# main.net
KiCad netlist of a schematic drawn in Altium Designer
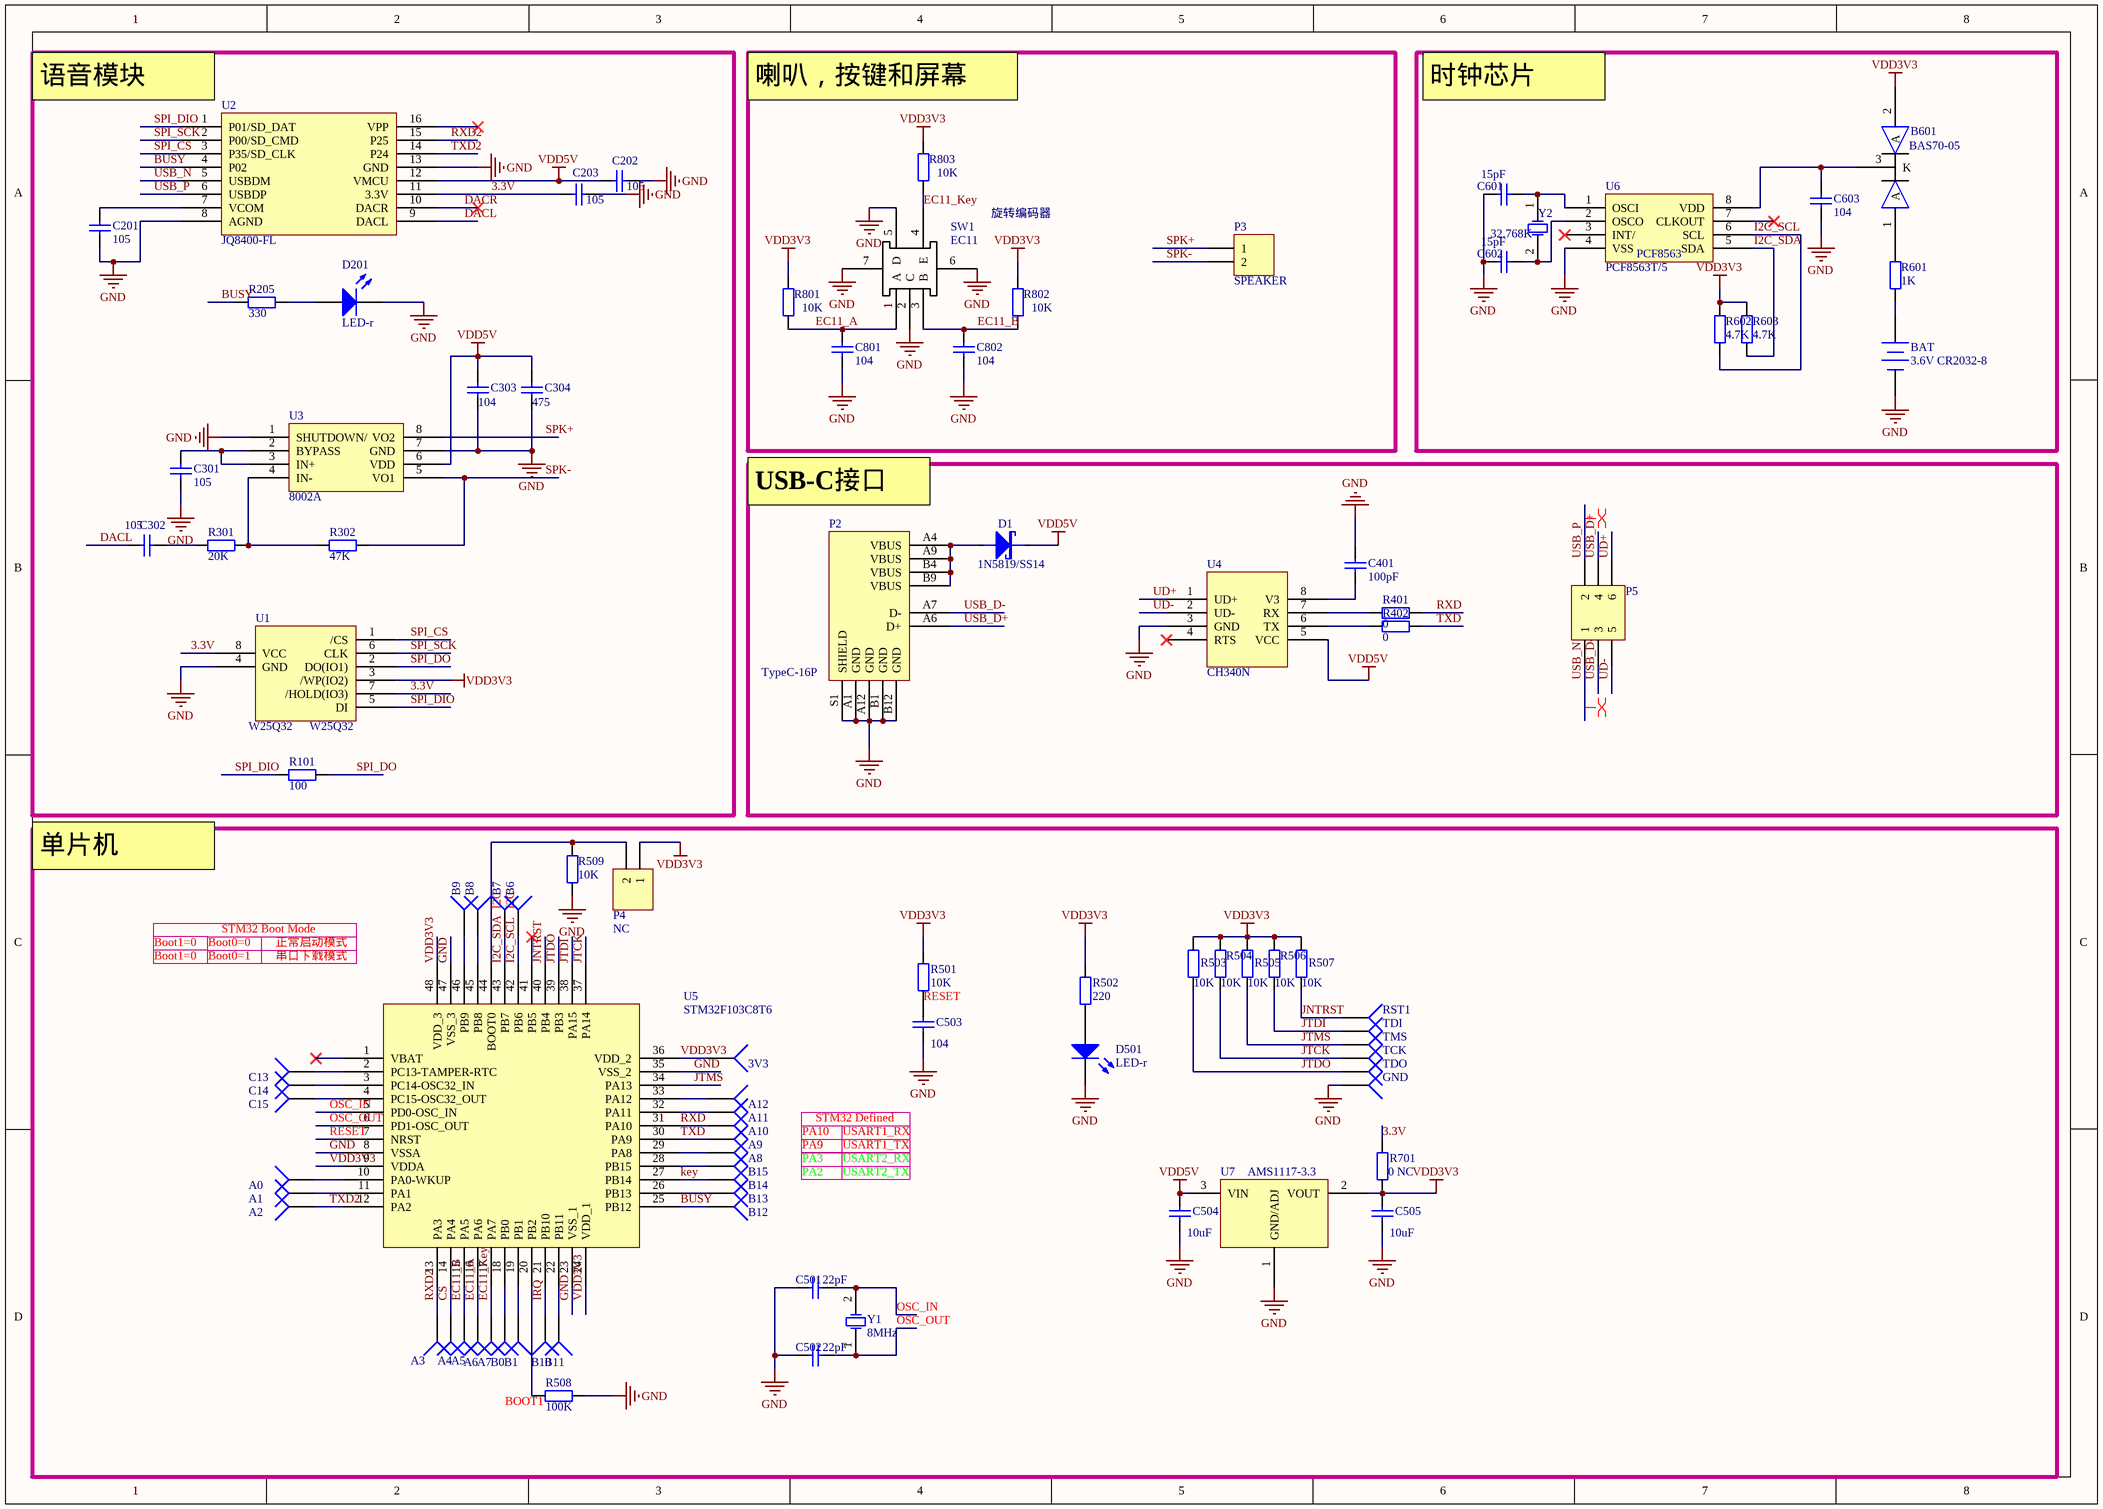
[diagram p0: main.SchDoc]

(export (version "E")
  (design (tool "Eeschema 10.0.6"))
  (components
    (comp (ref "3V3")
      (value "Socket")
      (footprint "TP")
      (fields (field (name "PUBLISHER") "Altium Limited"))
      (libsource (lib "Miscellaneous Connectors") (part "Socket"))
    )
    (comp (ref "A0")
      (value "Socket")
      (footprint "TP")
      (fields (field (name "PUBLISHER") "Altium Limited"))
      (libsource (lib "Miscellaneous Connectors") (part "Socket"))
    )
    (comp (ref "A1")
      (value "Socket")
      (footprint "TP")
      (fields (field (name "PUBLISHER") "Altium Limited"))
      (libsource (lib "Miscellaneous Connectors") (part "Socket"))
    )
    (comp (ref "A2")
      (value "Socket")
      (footprint "TP")
      (fields (field (name "PUBLISHER") "Altium Limited"))
      (libsource (lib "Miscellaneous Connectors") (part "Socket"))
    )
    (comp (ref "A3")
      (value "Socket")
      (footprint "TP")
      (fields (field (name "PUBLISHER") "Altium Limited"))
      (libsource (lib "Miscellaneous Connectors") (part "Socket"))
    )
    (comp (ref "A4")
      (value "Socket")
      (footprint "TP")
      (fields (field (name "PUBLISHER") "Altium Limited"))
      (libsource (lib "Miscellaneous Connectors") (part "Socket"))
    )
    (comp (ref "A5")
      (value "Socket")
      (footprint "TP")
      (fields (field (name "PUBLISHER") "Altium Limited"))
      (libsource (lib "Miscellaneous Connectors") (part "Socket"))
    )
    (comp (ref "A6")
      (value "Socket")
      (footprint "TP")
      (fields (field (name "PUBLISHER") "Altium Limited"))
      (libsource (lib "Miscellaneous Connectors") (part "Socket"))
    )
    (comp (ref "A7")
      (value "Socket")
      (footprint "TP")
      (fields (field (name "PUBLISHER") "Altium Limited"))
      (libsource (lib "Miscellaneous Connectors") (part "Socket"))
    )
    (comp (ref "A8")
      (value "Socket")
      (footprint "TP")
      (fields (field (name "PUBLISHER") "Altium Limited"))
      (libsource (lib "Miscellaneous Connectors") (part "Socket"))
    )
    (comp (ref "A9")
      (value "Socket")
      (footprint "TP")
      (fields (field (name "PUBLISHER") "Altium Limited"))
      (libsource (lib "Miscellaneous Connectors") (part "Socket"))
    )
    (comp (ref "A10")
      (value "Socket")
      (footprint "TP")
      (fields (field (name "PUBLISHER") "Altium Limited"))
      (libsource (lib "Miscellaneous Connectors") (part "Socket"))
    )
    (comp (ref "A11")
      (value "Socket")
      (footprint "TP")
      (fields (field (name "PUBLISHER") "Altium Limited"))
      (libsource (lib "Miscellaneous Connectors") (part "Socket"))
    )
    (comp (ref "A12")
      (value "Socket")
      (footprint "TP")
      (fields (field (name "PUBLISHER") "Altium Limited"))
      (libsource (lib "Miscellaneous Connectors") (part "Socket"))
    )
    (comp (ref "B0")
      (value "Socket")
      (footprint "TP")
      (fields (field (name "PUBLISHER") "Altium Limited"))
      (libsource (lib "Miscellaneous Connectors") (part "Socket"))
    )
    (comp (ref "B1")
      (value "Socket")
      (footprint "TP")
      (fields (field (name "PUBLISHER") "Altium Limited"))
      (libsource (lib "Miscellaneous Connectors") (part "Socket"))
    )
    (comp (ref "B6")
      (value "Socket")
      (footprint "TP")
      (fields (field (name "PUBLISHER") "Altium Limited"))
      (libsource (lib "Miscellaneous Connectors") (part "Socket"))
    )
    (comp (ref "B7")
      (value "Socket")
      (footprint "TP")
      (fields (field (name "PUBLISHER") "Altium Limited"))
      (libsource (lib "Miscellaneous Connectors") (part "Socket"))
    )
    (comp (ref "B8")
      (value "Socket")
      (footprint "TP")
      (fields (field (name "PUBLISHER") "Altium Limited"))
      (libsource (lib "Miscellaneous Connectors") (part "Socket"))
    )
    (comp (ref "B9")
      (value "Socket")
      (footprint "TP")
      (fields (field (name "PUBLISHER") "Altium Limited"))
      (libsource (lib "Miscellaneous Connectors") (part "Socket"))
    )
    (comp (ref "B10")
      (value "Socket")
      (footprint "TP")
      (fields (field (name "PUBLISHER") "Altium Limited"))
      (libsource (lib "Miscellaneous Connectors") (part "Socket"))
    )
    (comp (ref "B11")
      (value "Socket")
      (footprint "TP")
      (fields (field (name "PUBLISHER") "Altium Limited"))
      (libsource (lib "Miscellaneous Connectors") (part "Socket"))
    )
    (comp (ref "B12")
      (value "Socket")
      (footprint "TP")
      (fields (field (name "PUBLISHER") "Altium Limited"))
      (libsource (lib "Miscellaneous Connectors") (part "Socket"))
    )
    (comp (ref "B13")
      (value "Socket")
      (footprint "TP")
      (fields (field (name "PUBLISHER") "Altium Limited"))
      (libsource (lib "Miscellaneous Connectors") (part "Socket"))
    )
    (comp (ref "B14")
      (value "Socket")
      (footprint "TP")
      (fields (field (name "PUBLISHER") "Altium Limited"))
      (libsource (lib "Miscellaneous Connectors") (part "Socket"))
    )
    (comp (ref "B15")
      (value "Socket")
      (footprint "TP")
      (fields (field (name "PUBLISHER") "Altium Limited"))
      (libsource (lib "Miscellaneous Connectors") (part "Socket"))
    )
    (comp (ref "B601")
      (value "BAS70-05")
      (footprint "SMT_TRIODE_NPN")
      (description "贴片三极管  丝印75")
      (libsource (lib "Hardware") (part "BAS70 74"))
    )
    (comp (ref "BAT")
      (value "3.6V CR2032-8")
      (footprint "CR2032-8")
      (description "电池座 半圆形")
      (fields (field (name "PUBLISHER") "Altium Limited"))
      (libsource (lib "Miscellaneous Devices") (part "Battery"))
    )
    (comp (ref "C13")
      (value "Socket")
      (footprint "TP")
      (fields (field (name "PUBLISHER") "Altium Limited"))
      (libsource (lib "Miscellaneous Connectors") (part "Socket"))
    )
    (comp (ref "C14")
      (value "Socket")
      (footprint "TP")
      (fields (field (name "PUBLISHER") "Altium Limited"))
      (libsource (lib "Miscellaneous Connectors") (part "Socket"))
    )
    (comp (ref "C15")
      (value "Socket")
      (footprint "TP")
      (fields (field (name "PUBLISHER") "Altium Limited"))
      (libsource (lib "Miscellaneous Connectors") (part "Socket"))
    )
    (comp (ref "C201")
      (value "105")
      (footprint "0603_CAP")
      (description "Capacitor 0603")
      (fields (field (name "PUBLISHER") "Altium Limited"))
      (libsource (lib "Miscellaneous Devices") (part "Cap"))
    )
    (comp (ref "C202")
      (value "105")
      (footprint "0603_CAP")
      (description "Capacitor 0603")
      (fields (field (name "PUBLISHER") "Altium Limited"))
      (libsource (lib "Miscellaneous Devices") (part "Cap"))
    )
    (comp (ref "C203")
      (value "105")
      (footprint "0603_CAP")
      (description "Capacitor 0603")
      (fields (field (name "PUBLISHER") "Altium Limited"))
      (libsource (lib "Miscellaneous Devices") (part "Cap"))
    )
    (comp (ref "C301")
      (value "105")
      (footprint "0603_CAP")
      (description "Capacitor 0603")
      (fields (field (name "PUBLISHER") "Altium Limited"))
      (libsource (lib "Miscellaneous Devices") (part "Cap"))
    )
    (comp (ref "C302")
      (value "105")
      (footprint "0603_CAP")
      (description "Capacitor 0603")
      (fields (field (name "PUBLISHER") "Altium Limited"))
      (libsource (lib "Miscellaneous Devices") (part "Cap"))
    )
    (comp (ref "C303")
      (value "104")
      (footprint "0603_CAP")
      (description "Capacitor 0603")
      (fields (field (name "PUBLISHER") "Altium Limited"))
      (libsource (lib "Miscellaneous Devices") (part "Cap"))
    )
    (comp (ref "C304")
      (value "475")
      (footprint "0603_CAP")
      (description "Capacitor 0603")
      (fields (field (name "PUBLISHER") "Altium Limited"))
      (libsource (lib "Miscellaneous Devices") (part "Cap"))
    )
    (comp (ref "C401")
      (value "100pF")
      (footprint "0603_CAP")
      (description "Capacitor 0603")
      (fields (field (name "PUBLISHER") "Altium Limited"))
      (libsource (lib "Miscellaneous Devices") (part "Cap"))
    )
    (comp (ref "C501")
      (value "22pF")
      (footprint "0603_CAP")
      (description "Capacitor 0603")
      (fields (field (name "PUBLISHER") "Altium Limited"))
      (libsource (lib "Miscellaneous Devices") (part "Cap"))
    )
    (comp (ref "C502")
      (value "22pF")
      (footprint "0603_CAP")
      (description "Capacitor 0603")
      (fields (field (name "PUBLISHER") "Altium Limited"))
      (libsource (lib "Miscellaneous Devices") (part "Cap"))
    )
    (comp (ref "C503")
      (value "104")
      (footprint "0603_CAP")
      (description "Capacitor 0603")
      (fields (field (name "PUBLISHER") "Altium Limited"))
      (libsource (lib "Miscellaneous Devices") (part "Cap"))
    )
    (comp (ref "C504")
      (value "10uF")
      (footprint "0603_CAP")
      (description "Capacitor 0603")
      (fields (field (name "PUBLISHER") "Altium Limited"))
      (libsource (lib "Miscellaneous Devices") (part "Cap"))
    )
    (comp (ref "C505")
      (value "10uF")
      (footprint "0603_CAP")
      (description "Capacitor 0603")
      (fields (field (name "PUBLISHER") "Altium Limited"))
      (libsource (lib "Miscellaneous Devices") (part "Cap"))
    )
    (comp (ref "C601")
      (value "15pF")
      (footprint "0603_CAP")
      (description "Capacitor 0603")
      (fields (field (name "PUBLISHER") "Altium Limited"))
      (libsource (lib "Miscellaneous Devices") (part "Cap"))
    )
    (comp (ref "C602")
      (value "15pF")
      (footprint "0603_CAP")
      (description "Capacitor 0603")
      (fields (field (name "PUBLISHER") "Altium Limited"))
      (libsource (lib "Miscellaneous Devices") (part "Cap"))
    )
    (comp (ref "C603")
      (value "104")
      (footprint "0603_CAP")
      (description "Capacitor 0603")
      (fields (field (name "PUBLISHER") "Altium Limited"))
      (libsource (lib "Miscellaneous Devices") (part "Cap"))
    )
    (comp (ref "C801")
      (value "104")
      (footprint "0603_CAP")
      (description "Capacitor 0603")
      (fields (field (name "PUBLISHER") "Altium Limited"))
      (libsource (lib "Miscellaneous Devices") (part "Cap"))
    )
    (comp (ref "C802")
      (value "104")
      (footprint "0603_CAP")
      (description "Capacitor 0603")
      (fields (field (name "PUBLISHER") "Altium Limited"))
      (libsource (lib "Miscellaneous Devices") (part "Cap"))
    )
    (comp (ref "D1")
      (value "1N5819/SS14")
      (footprint "SMA")
      (description "肖特基整流二极管SOD-323")
      (libsource (lib "Vowstar_Basic_Device") (part "SMT_DIODE_SCHOTTKY_SOD_323"))
    )
    (comp (ref "D201")
      (value "LED-r")
      (footprint "LED-0603")
      (description "NC")
      (fields (field (name "PUBLISHER") "Altium Limited"))
      (libsource (lib "Miscellaneous Devices") (part "LED2"))
    )
    (comp (ref "D501")
      (value "LED-r")
      (footprint "LED-0603")
      (description "NC")
      (fields (field (name "PUBLISHER") "Altium Limited"))
      (libsource (lib "Miscellaneous Devices") (part "LED2"))
    )
    (comp (ref "GND")
      (value "Socket")
      (footprint "TP")
      (fields (field (name "PUBLISHER") "Altium Limited"))
      (libsource (lib "Miscellaneous Connectors") (part "Socket"))
    )
    (comp (ref "P2")
      (value "TypeC-16P")
      (footprint "type-c 16pin")
      (description "TypeC接口16P")
      (libsource (lib "Hardware") (part "TypeC-16P"))
    )
    (comp (ref "P3")
      (value "SPEAKER")
      (footprint "Speaker")
      (description "扬声器")
      (fields (field (name "PUBLISHER") "Altium Limited"))
      (libsource (lib "Miscellaneous Connectors") (part "Header 2"))
    )
    (comp (ref "P4")
      (value "NC")
      (footprint "HDR1X2")
      (description "下载短接口")
      (fields (field (name "PUBLISHER") "Altium Limited"))
      (libsource (lib "") (part "Header 2_1"))
    )
    (comp (ref "P5")
      (value "NC 3X2")
      (footprint "HDR2X3")
      (description "USB跳线接口")
      (fields (field (name "PUBLISHER") "Altium Limited"))
      (libsource (lib "Miscellaneous Connectors") (part "Header 3X2"))
    )
    (comp (ref "R101")
      (value "100")
      (footprint "0603_CAP")
      (description "Resistor 0603")
      (fields (field (name "PUBLISHER") "Altium Limited"))
      (libsource (lib "") (part "Res2_1"))
    )
    (comp (ref "R205")
      (value "330")
      (footprint "0603_CAP")
      (description "Resistor 0603")
      (fields (field (name "PUBLISHER") "Altium Limited"))
      (libsource (lib "") (part "Res2_1"))
    )
    (comp (ref "R301")
      (value "20K")
      (footprint "0603_CAP")
      (description "Resistor 0603")
      (fields (field (name "PUBLISHER") "Altium Limited"))
      (libsource (lib "") (part "Res2_1"))
    )
    (comp (ref "R302")
      (value "47K")
      (footprint "0603_CAP")
      (description "Resistor 0603")
      (fields (field (name "PUBLISHER") "Altium Limited"))
      (libsource (lib "") (part "Res2_1"))
    )
    (comp (ref "R401")
      (value "0")
      (footprint "0603_CAP")
      (description "Resistor 0603")
      (fields (field (name "PUBLISHER") "Altium Limited"))
      (libsource (lib "") (part "Res2_2"))
    )
    (comp (ref "R402")
      (value "0")
      (footprint "0603_CAP")
      (description "Resistor 0603")
      (fields (field (name "PUBLISHER") "Altium Limited"))
      (libsource (lib "") (part "Res2_2"))
    )
    (comp (ref "R501")
      (value "10K")
      (footprint "0603_CAP")
      (description "Resistor 0603")
      (fields (field (name "PUBLISHER") "Altium Limited"))
      (libsource (lib "Miscellaneous Devices") (part "Res2"))
    )
    (comp (ref "R502")
      (value "220")
      (footprint "0603_CAP")
      (description "Resistor 0603")
      (fields (field (name "PUBLISHER") "Altium Limited"))
      (libsource (lib "Miscellaneous Devices") (part "Res2"))
    )
    (comp (ref "R503")
      (value "10K")
      (footprint "0603_CAP")
      (description "Resistor 0603")
      (fields (field (name "PUBLISHER") "Altium Limited"))
      (libsource (lib "Miscellaneous Devices") (part "Res2"))
    )
    (comp (ref "R504")
      (value "10K")
      (footprint "0603_CAP")
      (description "Resistor 0603")
      (fields (field (name "PUBLISHER") "Altium Limited"))
      (libsource (lib "Miscellaneous Devices") (part "Res2"))
    )
    (comp (ref "R505")
      (value "10K")
      (footprint "0603_CAP")
      (description "Resistor 0603")
      (fields (field (name "PUBLISHER") "Altium Limited"))
      (libsource (lib "Miscellaneous Devices") (part "Res2"))
    )
    (comp (ref "R506")
      (value "10K")
      (footprint "0603_CAP")
      (description "Resistor 0603")
      (fields (field (name "PUBLISHER") "Altium Limited"))
      (libsource (lib "Miscellaneous Devices") (part "Res2"))
    )
    (comp (ref "R507")
      (value "10K")
      (footprint "0603_CAP")
      (description "Resistor 0603")
      (fields (field (name "PUBLISHER") "Altium Limited"))
      (libsource (lib "Miscellaneous Devices") (part "Res2"))
    )
    (comp (ref "R508")
      (value "100K")
      (footprint "0603_CAP")
      (description "Resistor 0603")
      (fields (field (name "PUBLISHER") "Altium Limited"))
      (libsource (lib "") (part "Res2_2"))
    )
    (comp (ref "R509")
      (value "10K")
      (footprint "0603_CAP")
      (description "Resistor 0603")
      (fields (field (name "PUBLISHER") "Altium Limited"))
      (libsource (lib "Miscellaneous Devices") (part "Res2"))
    )
    (comp (ref "R601")
      (value "1K")
      (footprint "0603_CAP")
      (description "Resistor 0603")
      (fields (field (name "PUBLISHER") "Altium Limited"))
      (libsource (lib "Miscellaneous Devices") (part "Res2"))
    )
    (comp (ref "R602")
      (value "4.7K")
      (footprint "0603_CAP")
      (description "Resistor 0603")
      (fields (field (name "PUBLISHER") "Altium Limited"))
      (libsource (lib "Miscellaneous Devices") (part "Res2"))
    )
    (comp (ref "R603")
      (value "4.7K")
      (footprint "0603_CAP")
      (description "Resistor 0603")
      (fields (field (name "PUBLISHER") "Altium Limited"))
      (libsource (lib "Miscellaneous Devices") (part "Res2"))
    )
    (comp (ref "R701")
      (value "0 NC")
      (footprint "0603_CAP")
      (description "Resistor 0603")
      (fields (field (name "PUBLISHER") "Altium Limited"))
      (libsource (lib "Miscellaneous Devices") (part "Res2"))
    )
    (comp (ref "R801")
      (value "10K")
      (footprint "0603_CAP")
      (description "Resistor 0603")
      (fields (field (name "PUBLISHER") "Altium Limited"))
      (libsource (lib "") (part "Res2_3"))
    )
    (comp (ref "R802")
      (value "10K")
      (footprint "0603_CAP")
      (description "Resistor 0603")
      (fields (field (name "PUBLISHER") "Altium Limited"))
      (libsource (lib "") (part "Res2_3"))
    )
    (comp (ref "R803")
      (value "10K")
      (footprint "0603_CAP")
      (description "Resistor 0603")
      (fields (field (name "PUBLISHER") "Altium Limited"))
      (libsource (lib "") (part "Res2_3"))
    )
    (comp (ref "RST1")
      (value "Socket")
      (footprint "TP")
      (fields (field (name "PUBLISHER") "Altium Limited"))
      (libsource (lib "Miscellaneous Connectors") (part "Socket"))
    )
    (comp (ref "SW1")
      (value "EC11")
      (footprint "EC11")
      (description "旋转编码器20脉冲")
      (libsource (lib "Hardware") (part "EC11"))
    )
    (comp (ref "TCK")
      (value "Socket")
      (footprint "TP")
      (fields (field (name "PUBLISHER") "Altium Limited"))
      (libsource (lib "Miscellaneous Connectors") (part "Socket"))
    )
    (comp (ref "TDI")
      (value "Socket")
      (footprint "TP")
      (fields (field (name "PUBLISHER") "Altium Limited"))
      (libsource (lib "Miscellaneous Connectors") (part "Socket"))
    )
    (comp (ref "TDO")
      (value "Socket")
      (footprint "TP")
      (fields (field (name "PUBLISHER") "Altium Limited"))
      (libsource (lib "Miscellaneous Connectors") (part "Socket"))
    )
    (comp (ref "TMS")
      (value "Socket")
      (footprint "TP")
      (fields (field (name "PUBLISHER") "Altium Limited"))
      (libsource (lib "Miscellaneous Connectors") (part "Socket"))
    )
    (comp (ref "U1")
      (value "W25Q32")
      (footprint "SOP8-208mil")
      (description "Flash")
      (libsource (lib "Hardware") (part "W25Q32"))
    )
    (comp (ref "U2")
      (value "JQ8400-FL")
      (footprint "JQF8400-FL")
      (description "语音芯片")
      (libsource (lib "Hardware") (part "JQ8400-FL"))
    )
    (comp (ref "U3")
      (value "8002A")
      (footprint "8002A")
      (description "3W功放")
      (libsource (lib "Hardware") (part "8002A"))
    )
    (comp (ref "U4")
      (value "CH340N")
      (footprint "SOP8")
      (description "U转串")
      (libsource (lib "clock") (part "ch340"))
    )
    (comp (ref "U5")
      (value "STM32F103C8T6")
      (footprint "LQFP48")
      (description "单片机")
      (libsource (lib "Hardware") (part "STM32F101CB"))
    )
    (comp (ref "U6")
      (value "PCF8563T/5")
      (footprint "PCF8563")
      (description "时钟芯片")
      (libsource (lib "Hardware") (part "PCF8563"))
    )
    (comp (ref "U7")
      (value "AMS1117-3.3")
      (footprint "SOT-223")
      (libsource (lib "Vowstar_IC_General") (part "NCP1117"))
    )
    (comp (ref "Y1")
      (value "8MHz")
      (footprint "CPU-crystal")
      (description "49S型直插无源晶振")
      (fields (field (name "PUBLISHER") "Altium Limited"))
      (libsource (lib "Miscellaneous Devices") (part "XTAL"))
    )
    (comp (ref "Y2")
      (value "32.768K")
      (footprint "Crystal")
      (description "圆柱型3*8mm无源晶振")
      (fields (field (name "PUBLISHER") "Altium Limited"))
      (libsource (lib "Miscellaneous Devices") (part "XTAL"))
    )
  )
  (nets
    (net (code "1") (name "/3.3V") (class "Default")
      (node (ref "C203") (pin "2") (pinfunction "2_2") (pintype "passive"))
      (node (ref "R701") (pin "2") (pinfunction "2_2") (pintype "passive"))
      (node (ref "U1") (pin "7") (pinfunction "/HOLD(IO3)_7") (pintype "passive"))
      (node (ref "U1") (pin "8") (pinfunction "VCC_8") (pintype "passive"))
      (node (ref "U2") (pin "11") (pinfunction "3.3V_11") (pintype "passive"))
    )
    (net (code "2") (name "/BUSY") (class "Default")
      (node (ref "B12") (pin "1") (pinfunction "1_1") (pintype "passive"))
      (node (ref "R205") (pin "2") (pinfunction "2_2") (pintype "passive"))
      (node (ref "U2") (pin "4") (pinfunction "P02_4") (pintype "passive"))
      (node (ref "U5") (pin "25") (pinfunction "PB12_25") (pintype "passive"))
    )
    (net (code "3") (name "/CS") (class "Default")
      (node (ref "A4") (pin "1") (pinfunction "1_1") (pintype "passive"))
      (node (ref "U5") (pin "14") (pinfunction "PA4_14") (pintype "passive"))
    )
    (net (code "4") (name "/DACL") (class "Default")
      (node (ref "C302") (pin "2") (pinfunction "2_2") (pintype "passive"))
      (node (ref "U2") (pin "9") (pinfunction "DACL_9") (pintype "passive"))
    )
    (net (code "5") (name "/DACR") (class "Default")
      (node (ref "U2") (pin "10") (pinfunction "DACR_10") (pintype "passive+no_connect"))
    )
    (net (code "6") (name "/EC11_A") (class "Default")
      (node (ref "A6") (pin "1") (pinfunction "1_1") (pintype "passive"))
      (node (ref "C801") (pin "1") (pinfunction "1_1") (pintype "passive"))
      (node (ref "R801") (pin "2") (pinfunction "2_2") (pintype "passive"))
      (node (ref "SW1") (pin "1") (pinfunction "A_1") (pintype "passive"))
      (node (ref "U5") (pin "16") (pinfunction "PA6_16") (pintype "passive"))
    )
    (net (code "7") (name "/EC11_B") (class "Default")
      (node (ref "A5") (pin "1") (pinfunction "1_1") (pintype "passive"))
      (node (ref "C802") (pin "1") (pinfunction "1_1") (pintype "passive"))
      (node (ref "R802") (pin "2") (pinfunction "2_2") (pintype "passive"))
      (node (ref "SW1") (pin "3") (pinfunction "B_3") (pintype "passive"))
      (node (ref "U5") (pin "15") (pinfunction "PA5_15") (pintype "passive"))
    )
    (net (code "8") (name "/EC11_Key") (class "Default")
      (node (ref "A7") (pin "1") (pinfunction "1_1") (pintype "passive"))
      (node (ref "R803") (pin "2") (pinfunction "2_2") (pintype "passive"))
      (node (ref "SW1") (pin "4") (pinfunction "E_4") (pintype "passive"))
      (node (ref "U5") (pin "17") (pinfunction "PA7_17") (pintype "passive"))
    )
    (net (code "9") (name "/I2C_SCL") (class "Default")
      (node (ref "B6") (pin "1") (pinfunction "1_1") (pintype "passive"))
      (node (ref "R602") (pin "1") (pinfunction "1_1") (pintype "passive"))
      (node (ref "U5") (pin "42") (pinfunction "PB6_42") (pintype "passive"))
      (node (ref "U6") (pin "6") (pinfunction "SCL_6") (pintype "passive"))
    )
    (net (code "10") (name "/I2C_SDA") (class "Default")
      (node (ref "B7") (pin "1") (pinfunction "1_1") (pintype "passive"))
      (node (ref "R603") (pin "1") (pinfunction "1_1") (pintype "passive"))
      (node (ref "U5") (pin "43") (pinfunction "PB7_43") (pintype "passive"))
      (node (ref "U6") (pin "5") (pinfunction "SDA_5") (pintype "passive"))
    )
    (net (code "11") (name "/IRQ") (class "Default")
      (node (ref "B10") (pin "1") (pinfunction "1_1") (pintype "passive"))
      (node (ref "U5") (pin "21") (pinfunction "PB10_21") (pintype "passive"))
    )
    (net (code "12") (name "/JNTRST") (class "Default")
      (node (ref "R507") (pin "1") (pinfunction "1_1") (pintype "passive"))
      (node (ref "RST1") (pin "1") (pinfunction "1_1") (pintype "passive"))
      (node (ref "U5") (pin "40") (pinfunction "PB4_40") (pintype "passive"))
    )
    (net (code "13") (name "/JTCK") (class "Default")
      (node (ref "R504") (pin "1") (pinfunction "1_1") (pintype "passive"))
      (node (ref "TCK") (pin "1") (pinfunction "1_1") (pintype "passive"))
      (node (ref "U5") (pin "37") (pinfunction "PA14_37") (pintype "passive"))
    )
    (net (code "14") (name "/JTDI") (class "Default")
      (node (ref "R506") (pin "1") (pinfunction "1_1") (pintype "passive"))
      (node (ref "TDI") (pin "1") (pinfunction "1_1") (pintype "passive"))
      (node (ref "U5") (pin "38") (pinfunction "PA15_38") (pintype "passive"))
    )
    (net (code "15") (name "/JTDO") (class "Default")
      (node (ref "R503") (pin "1") (pinfunction "1_1") (pintype "passive"))
      (node (ref "TDO") (pin "1") (pinfunction "1_1") (pintype "passive"))
      (node (ref "U5") (pin "39") (pinfunction "PB3_39") (pintype "passive"))
    )
    (net (code "16") (name "/JTMS") (class "Default")
      (node (ref "R505") (pin "1") (pinfunction "1_1") (pintype "passive"))
      (node (ref "TMS") (pin "1") (pinfunction "1_1") (pintype "passive"))
      (node (ref "U5") (pin "34") (pinfunction "PA13_34") (pintype "passive"))
    )
    (net (code "17") (name "/OSC_IN") (class "Default")
      (node (ref "C501") (pin "1") (pinfunction "1_1") (pintype "passive"))
      (node (ref "U5") (pin "5") (pinfunction "PD0-OSC_IN_5") (pintype "passive"))
      (node (ref "Y1") (pin "2") (pinfunction "OSC2_2") (pintype "passive"))
    )
    (net (code "18") (name "/OSC_OUT") (class "Default")
      (node (ref "C502") (pin "1") (pinfunction "1_1") (pintype "passive"))
      (node (ref "U5") (pin "6") (pinfunction "PD1-OSC_OUT_6") (pintype "passive"))
      (node (ref "Y1") (pin "1") (pinfunction "OSC1_1") (pintype "passive"))
    )
    (net (code "19") (name "/RESET") (class "Default")
      (node (ref "C503") (pin "1") (pinfunction "1_1") (pintype "passive"))
      (node (ref "R501") (pin "1") (pinfunction "1_1") (pintype "passive"))
      (node (ref "U5") (pin "7") (pinfunction "NRST_7") (pintype "passive"))
    )
    (net (code "20") (name "/RXD") (class "Default")
      (node (ref "A10") (pin "1") (pinfunction "1_1") (pintype "passive"))
      (node (ref "R401") (pin "2") (pinfunction "2_2") (pintype "passive"))
      (node (ref "U5") (pin "31") (pinfunction "PA10_31") (pintype "passive"))
    )
    (net (code "21") (name "/RXD2") (class "Default")
      (node (ref "A3") (pin "1") (pinfunction "1_1") (pintype "passive"))
      (node (ref "U2") (pin "15") (pinfunction "P25_15") (pintype "passive"))
      (node (ref "U5") (pin "13") (pinfunction "PA3_13") (pintype "passive"))
    )
    (net (code "22") (name "/SPI_CS") (class "Default")
      (node (ref "U1") (pin "1") (pinfunction "/CS_1") (pintype "passive"))
      (node (ref "U2") (pin "3") (pinfunction "P35/SD_CLK_3") (pintype "passive"))
    )
    (net (code "23") (name "/SPI_DIO") (class "Default")
      (node (ref "R101") (pin "2") (pinfunction "2_2") (pintype "passive"))
      (node (ref "U1") (pin "5") (pinfunction "DI_5") (pintype "passive"))
      (node (ref "U2") (pin "1") (pinfunction "P01/SD_DAT_1") (pintype "passive"))
    )
    (net (code "24") (name "/SPI_DO") (class "Default")
      (node (ref "R101") (pin "1") (pinfunction "1_1") (pintype "passive"))
      (node (ref "U1") (pin "2") (pinfunction "DO(IO1)_2") (pintype "passive"))
    )
    (net (code "25") (name "/SPI_SCK") (class "Default")
      (node (ref "U1") (pin "6") (pinfunction "CLK_6") (pintype "passive"))
      (node (ref "U2") (pin "2") (pinfunction "P00/SD_CMD_2") (pintype "passive"))
    )
    (net (code "26") (name "/SPK+") (class "Default")
      (node (ref "P3") (pin "1") (pinfunction "1_1") (pintype "passive"))
      (node (ref "U3") (pin "8") (pinfunction "VO2_8") (pintype "passive"))
    )
    (net (code "27") (name "/SPK-") (class "Default")
      (node (ref "P3") (pin "2") (pinfunction "2_2") (pintype "passive"))
      (node (ref "R302") (pin "1") (pinfunction "1_1") (pintype "passive"))
      (node (ref "U3") (pin "5") (pinfunction "VO1_5") (pintype "passive"))
    )
    (net (code "28") (name "/TXD") (class "Default")
      (node (ref "A9") (pin "1") (pinfunction "1_1") (pintype "passive"))
      (node (ref "R402") (pin "2") (pinfunction "2_2") (pintype "passive"))
      (node (ref "U5") (pin "30") (pinfunction "PA9_30") (pintype "passive"))
    )
    (net (code "29") (name "/TXD2") (class "Default")
      (node (ref "A2") (pin "1") (pinfunction "1_1") (pintype "passive"))
      (node (ref "U2") (pin "14") (pinfunction "P24_14") (pintype "passive"))
      (node (ref "U5") (pin "12") (pinfunction "PA2_12") (pintype "passive"))
    )
    (net (code "30") (name "/UD+") (class "Default")
      (node (ref "P5") (pin "6") (pinfunction "6_6") (pintype "passive"))
      (node (ref "U4") (pin "1") (pinfunction "UD+_1") (pintype "passive"))
    )
    (net (code "31") (name "/UD-") (class "Default")
      (node (ref "P5") (pin "5") (pinfunction "5_5") (pintype "passive"))
      (node (ref "U4") (pin "2") (pinfunction "UD-_2") (pintype "passive"))
    )
    (net (code "32") (name "/USB_D+") (class "Default")
      (node (ref "P2") (pin "A6") (pinfunction "D+_A6") (pintype "passive"))
      (node (ref "P5") (pin "4") (pinfunction "4_4") (pintype "passive"))
    )
    (net (code "33") (name "/USB_D-") (class "Default")
      (node (ref "P2") (pin "A7") (pinfunction "D-_A7") (pintype "passive"))
      (node (ref "P5") (pin "3") (pinfunction "3_3") (pintype "passive"))
    )
    (net (code "34") (name "/USB_N") (class "Default")
      (node (ref "P5") (pin "1") (pinfunction "1_1") (pintype "passive"))
      (node (ref "U2") (pin "5") (pinfunction "USBDM_5") (pintype "passive"))
    )
    (net (code "35") (name "/USB_P") (class "Default")
      (node (ref "P5") (pin "2") (pinfunction "2_2") (pintype "passive"))
      (node (ref "U2") (pin "6") (pinfunction "USBDP_6") (pintype "passive"))
    )
    (net (code "36") (name "/key") (class "Default")
      (node (ref "B14") (pin "1") (pinfunction "1_1") (pintype "passive"))
      (node (ref "U5") (pin "27") (pinfunction "PB14_27") (pintype "passive"))
    )
    (net (code "37") (name "GND") (class "Default")
      (node (ref "BAT") (pin "2") (pinfunction "-_2") (pintype "passive"))
      (node (ref "C201") (pin "1") (pinfunction "1_1") (pintype "passive"))
      (node (ref "C202") (pin "1") (pinfunction "1_1") (pintype "passive"))
      (node (ref "C203") (pin "1") (pinfunction "1_1") (pintype "passive"))
      (node (ref "C301") (pin "1") (pinfunction "1_1") (pintype "passive"))
      (node (ref "C303") (pin "2") (pinfunction "2_2") (pintype "passive"))
      (node (ref "C304") (pin "2") (pinfunction "2_2") (pintype "passive"))
      (node (ref "C401") (pin "2") (pinfunction "2_2") (pintype "passive"))
      (node (ref "C501") (pin "2") (pinfunction "2_2") (pintype "passive"))
      (node (ref "C502") (pin "2") (pinfunction "2_2") (pintype "passive"))
      (node (ref "C503") (pin "2") (pinfunction "2_2") (pintype "passive"))
      (node (ref "C504") (pin "2") (pinfunction "2_2") (pintype "passive"))
      (node (ref "C505") (pin "2") (pinfunction "2_2") (pintype "passive"))
      (node (ref "C601") (pin "2") (pinfunction "2_2") (pintype "passive"))
      (node (ref "C602") (pin "2") (pinfunction "2_2") (pintype "passive"))
      (node (ref "C603") (pin "2") (pinfunction "2_2") (pintype "passive"))
      (node (ref "C801") (pin "2") (pinfunction "2_2") (pintype "passive"))
      (node (ref "C802") (pin "2") (pinfunction "2_2") (pintype "passive"))
      (node (ref "D201") (pin "2") (pinfunction "K_2") (pintype "passive"))
      (node (ref "D501") (pin "2") (pinfunction "K_2") (pintype "passive"))
      (node (ref "GND") (pin "1") (pinfunction "1_1") (pintype "passive"))
      (node (ref "P2") (pin "A1") (pinfunction "GND_A1") (pintype "passive"))
      (node (ref "P2") (pin "A12") (pinfunction "GND_A12") (pintype "passive"))
      (node (ref "P2") (pin "B1") (pinfunction "GND_B1") (pintype "passive"))
      (node (ref "P2") (pin "B12") (pinfunction "GND_B12") (pintype "passive"))
      (node (ref "P2") (pin "S1") (pinfunction "SHIELD_S1") (pintype "passive"))
      (node (ref "R508") (pin "2") (pinfunction "2_2") (pintype "passive"))
      (node (ref "R509") (pin "1") (pinfunction "1_1") (pintype "passive"))
      (node (ref "SW1") (pin "2") (pinfunction "C_2") (pintype "passive"))
      (node (ref "SW1") (pin "5") (pinfunction "D_5") (pintype "passive"))
      (node (ref "SW1") (pin "6") (pinfunction "6_6") (pintype "passive"))
      (node (ref "SW1") (pin "7") (pinfunction "7_7") (pintype "passive"))
      (node (ref "U1") (pin "4") (pinfunction "GND_4") (pintype "passive"))
      (node (ref "U2") (pin "13") (pinfunction "GND_13") (pintype "passive"))
      (node (ref "U2") (pin "8") (pinfunction "AGND_8") (pintype "passive"))
      (node (ref "U3") (pin "1") (pinfunction "SHUTDOWN/_1") (pintype "passive"))
      (node (ref "U3") (pin "7") (pinfunction "GND_7") (pintype "passive"))
      (node (ref "U4") (pin "3") (pinfunction "GND_3") (pintype "passive"))
      (node (ref "U5") (pin "23") (pinfunction "VSS_1_23") (pintype "passive"))
      (node (ref "U5") (pin "35") (pinfunction "VSS_2_35") (pintype "passive"))
      (node (ref "U5") (pin "47") (pinfunction "VSS_3_47") (pintype "passive"))
      (node (ref "U5") (pin "8") (pinfunction "VSSA_8") (pintype "passive"))
      (node (ref "U6") (pin "4") (pinfunction "VSS_4") (pintype "passive"))
      (node (ref "U7") (pin "1") (pinfunction "GND/ADJ_1") (pintype "passive"))
    )
    (net (code "38") (name "Net-(B601-A-Pad1)") (class "Default")
      (node (ref "B601") (pin "1") (pinfunction "A_1") (pintype "passive"))
      (node (ref "R601") (pin "2") (pinfunction "2_2") (pintype "passive"))
    )
    (net (code "39") (name "Net-(B601-K)") (class "Default")
      (node (ref "B601") (pin "3") (pinfunction "K_3") (pintype "passive"))
      (node (ref "C603") (pin "1") (pinfunction "1_1") (pintype "passive"))
      (node (ref "U6") (pin "8") (pinfunction "VDD_8") (pintype "passive"))
    )
    (net (code "40") (name "Net-(BAT-+)") (class "Default")
      (node (ref "BAT") (pin "1") (pinfunction "+_1") (pintype "passive"))
      (node (ref "R601") (pin "1") (pinfunction "1_1") (pintype "passive"))
    )
    (net (code "41") (name "Net-(C302-Pad1)") (class "Default")
      (node (ref "C302") (pin "1") (pinfunction "1_1") (pintype "passive"))
      (node (ref "R301") (pin "2") (pinfunction "2_2") (pintype "passive"))
    )
    (net (code "42") (name "Net-(D1-A)") (class "Default")
      (node (ref "D1") (pin "1") (pinfunction "A_1") (pintype "passive"))
      (node (ref "P2") (pin "A4") (pinfunction "VBUS_A4") (pintype "passive"))
      (node (ref "P2") (pin "A9") (pinfunction "VBUS_A9") (pintype "passive"))
      (node (ref "P2") (pin "B4") (pinfunction "VBUS_B4") (pintype "passive"))
      (node (ref "P2") (pin "B9") (pinfunction "VBUS_B9") (pintype "passive"))
    )
    (net (code "43") (name "Net-(D201-A)") (class "Default")
      (node (ref "D201") (pin "1") (pinfunction "A_1") (pintype "passive"))
      (node (ref "R205") (pin "1") (pinfunction "1_1") (pintype "passive"))
    )
    (net (code "44") (name "Net-(D501-A)") (class "Default")
      (node (ref "D501") (pin "1") (pinfunction "A_1") (pintype "passive"))
      (node (ref "R502") (pin "1") (pinfunction "1_1") (pintype "passive"))
    )
    (net (code "45") (name "Net-(U2-VCOM)") (class "Default")
      (node (ref "C201") (pin "2") (pinfunction "2_2") (pintype "passive"))
      (node (ref "U2") (pin "7") (pinfunction "VCOM_7") (pintype "passive"))
    )
    (net (code "46") (name "Net-(U3-BYPASS)") (class "Default")
      (node (ref "C301") (pin "2") (pinfunction "2_2") (pintype "passive"))
      (node (ref "U3") (pin "2") (pinfunction "BYPASS_2") (pintype "passive"))
      (node (ref "U3") (pin "3") (pinfunction "IN+_3") (pintype "passive"))
    )
    (net (code "47") (name "Net-(U3-IN-)") (class "Default")
      (node (ref "R301") (pin "1") (pinfunction "1_1") (pintype "passive"))
      (node (ref "R302") (pin "2") (pinfunction "2_2") (pintype "passive"))
      (node (ref "U3") (pin "4") (pinfunction "IN-_4") (pintype "passive"))
    )
    (net (code "48") (name "Net-(U4-RX)") (class "Default")
      (node (ref "R401") (pin "1") (pinfunction "1_1") (pintype "passive"))
      (node (ref "U4") (pin "7") (pinfunction "RX_7") (pintype "passive"))
    )
    (net (code "49") (name "Net-(U4-TX)") (class "Default")
      (node (ref "R402") (pin "1") (pinfunction "1_1") (pintype "passive"))
      (node (ref "U4") (pin "6") (pinfunction "TX_6") (pintype "passive"))
    )
    (net (code "50") (name "Net-(U4-V3)") (class "Default")
      (node (ref "C401") (pin "1") (pinfunction "1_1") (pintype "passive"))
      (node (ref "U4") (pin "8") (pinfunction "V3_8") (pintype "passive"))
    )
    (net (code "51") (name "Net-(U5-BOOT0)") (class "Default")
      (node (ref "P4") (pin "2") (pinfunction "2_2") (pintype "passive"))
      (node (ref "R509") (pin "2") (pinfunction "2_2") (pintype "passive"))
      (node (ref "U5") (pin "44") (pinfunction "BOOT0_44") (pintype "passive"))
    )
    (net (code "52") (name "Net-(U5-PA0-WKUP)") (class "Default")
      (node (ref "A0") (pin "1") (pinfunction "1_1") (pintype "passive"))
      (node (ref "U5") (pin "10") (pinfunction "PA0-WKUP_10") (pintype "passive"))
    )
    (net (code "53") (name "Net-(U5-PA1)") (class "Default")
      (node (ref "A1") (pin "1") (pinfunction "1_1") (pintype "passive"))
      (node (ref "U5") (pin "11") (pinfunction "PA1_11") (pintype "passive"))
    )
    (net (code "54") (name "Net-(U5-PA8)") (class "Default")
      (node (ref "A8") (pin "1") (pinfunction "1_1") (pintype "passive"))
      (node (ref "U5") (pin "29") (pinfunction "PA8_29") (pintype "passive"))
    )
    (net (code "55") (name "Net-(U5-PA11)") (class "Default")
      (node (ref "A11") (pin "1") (pinfunction "1_1") (pintype "passive"))
      (node (ref "U5") (pin "32") (pinfunction "PA11_32") (pintype "passive"))
    )
    (net (code "56") (name "Net-(U5-PA12)") (class "Default")
      (node (ref "A12") (pin "1") (pinfunction "1_1") (pintype "passive"))
      (node (ref "U5") (pin "33") (pinfunction "PA12_33") (pintype "passive"))
    )
    (net (code "57") (name "Net-(U5-PB0)") (class "Default")
      (node (ref "B0") (pin "1") (pinfunction "1_1") (pintype "passive"))
      (node (ref "U5") (pin "18") (pinfunction "PB0_18") (pintype "passive"))
    )
    (net (code "58") (name "Net-(U5-PB1)") (class "Default")
      (node (ref "B1") (pin "1") (pinfunction "1_1") (pintype "passive"))
      (node (ref "U5") (pin "19") (pinfunction "PB1_19") (pintype "passive"))
    )
    (net (code "59") (name "Net-(U5-PB2)") (class "Default")
      (node (ref "R508") (pin "1") (pinfunction "1_1") (pintype "passive"))
      (node (ref "U5") (pin "20") (pinfunction "PB2_20") (pintype "passive"))
    )
    (net (code "60") (name "Net-(U5-PB8)") (class "Default")
      (node (ref "B8") (pin "1") (pinfunction "1_1") (pintype "passive"))
      (node (ref "U5") (pin "45") (pinfunction "PB8_45") (pintype "passive"))
    )
    (net (code "61") (name "Net-(U5-PB9)") (class "Default")
      (node (ref "B9") (pin "1") (pinfunction "1_1") (pintype "passive"))
      (node (ref "U5") (pin "46") (pinfunction "PB9_46") (pintype "passive"))
    )
    (net (code "62") (name "Net-(U5-PB11)") (class "Default")
      (node (ref "B11") (pin "1") (pinfunction "1_1") (pintype "passive"))
      (node (ref "U5") (pin "22") (pinfunction "PB11_22") (pintype "passive"))
    )
    (net (code "63") (name "Net-(U5-PB13)") (class "Default")
      (node (ref "B13") (pin "1") (pinfunction "1_1") (pintype "passive"))
      (node (ref "U5") (pin "26") (pinfunction "PB13_26") (pintype "passive"))
    )
    (net (code "64") (name "Net-(U5-PB15)") (class "Default")
      (node (ref "B15") (pin "1") (pinfunction "1_1") (pintype "passive"))
      (node (ref "U5") (pin "28") (pinfunction "PB15_28") (pintype "passive"))
    )
    (net (code "65") (name "Net-(U5-PC13-TAMPER-RTC)") (class "Default")
      (node (ref "C13") (pin "1") (pinfunction "1_1") (pintype "passive"))
      (node (ref "U5") (pin "2") (pinfunction "PC13-TAMPER-RTC_2") (pintype "passive"))
    )
    (net (code "66") (name "Net-(U5-PC14-OSC32_IN)") (class "Default")
      (node (ref "C14") (pin "1") (pinfunction "1_1") (pintype "passive"))
      (node (ref "U5") (pin "3") (pinfunction "PC14-OSC32_IN_3") (pintype "passive"))
    )
    (net (code "67") (name "Net-(U5-PC15-OSC32_OUT)") (class "Default")
      (node (ref "C15") (pin "1") (pinfunction "1_1") (pintype "passive"))
      (node (ref "U5") (pin "4") (pinfunction "PC15-OSC32_OUT_4") (pintype "passive"))
    )
    (net (code "68") (name "Net-(U6-OSCI)") (class "Default")
      (node (ref "C601") (pin "1") (pinfunction "1_1") (pintype "passive"))
      (node (ref "U6") (pin "1") (pinfunction "OSCI_1") (pintype "passive"))
      (node (ref "Y2") (pin "1") (pinfunction "OSC1_1") (pintype "passive"))
    )
    (net (code "69") (name "Net-(U6-OSCO)") (class "Default")
      (node (ref "C602") (pin "1") (pinfunction "1_1") (pintype "passive"))
      (node (ref "U6") (pin "2") (pinfunction "OSCO_2") (pintype "passive"))
      (node (ref "Y2") (pin "2") (pinfunction "OSC2_2") (pintype "passive"))
    )
    (net (code "70") (name "VDD3V3") (class "Default")
      (node (ref "3V3") (pin "1") (pinfunction "1_1") (pintype "passive"))
      (node (ref "B601") (pin "2") (pinfunction "A_2") (pintype "passive"))
      (node (ref "C505") (pin "1") (pinfunction "1_1") (pintype "passive"))
      (node (ref "P4") (pin "1") (pinfunction "1_1") (pintype "passive"))
      (node (ref "R501") (pin "2") (pinfunction "2_2") (pintype "passive"))
      (node (ref "R502") (pin "2") (pinfunction "2_2") (pintype "passive"))
      (node (ref "R503") (pin "2") (pinfunction "2_2") (pintype "passive"))
      (node (ref "R504") (pin "2") (pinfunction "2_2") (pintype "passive"))
      (node (ref "R505") (pin "2") (pinfunction "2_2") (pintype "passive"))
      (node (ref "R506") (pin "2") (pinfunction "2_2") (pintype "passive"))
      (node (ref "R507") (pin "2") (pinfunction "2_2") (pintype "passive"))
      (node (ref "R602") (pin "2") (pinfunction "2_2") (pintype "passive"))
      (node (ref "R603") (pin "2") (pinfunction "2_2") (pintype "passive"))
      (node (ref "R701") (pin "1") (pinfunction "1_1") (pintype "passive"))
      (node (ref "R801") (pin "1") (pinfunction "1_1") (pintype "passive"))
      (node (ref "R802") (pin "1") (pinfunction "1_1") (pintype "passive"))
      (node (ref "R803") (pin "1") (pinfunction "1_1") (pintype "passive"))
      (node (ref "U1") (pin "3") (pinfunction "/WP(IO2)_3") (pintype "passive"))
      (node (ref "U5") (pin "24") (pinfunction "VDD_1_24") (pintype "passive"))
      (node (ref "U5") (pin "36") (pinfunction "VDD_2_36") (pintype "passive"))
      (node (ref "U5") (pin "48") (pinfunction "VDD_3_48") (pintype "passive"))
      (node (ref "U5") (pin "9") (pinfunction "VDDA_9") (pintype "passive"))
      (node (ref "U7") (pin "2") (pinfunction "VOUT_2") (pintype "passive"))
    )
    (net (code "71") (name "VDD5V") (class "Default")
      (node (ref "C202") (pin "2") (pinfunction "2_2") (pintype "passive"))
      (node (ref "C303") (pin "1") (pinfunction "1_1") (pintype "passive"))
      (node (ref "C304") (pin "1") (pinfunction "1_1") (pintype "passive"))
      (node (ref "C504") (pin "1") (pinfunction "1_1") (pintype "passive"))
      (node (ref "D1") (pin "2") (pinfunction "K_2") (pintype "passive"))
      (node (ref "U2") (pin "12") (pinfunction "VMCU_12") (pintype "passive"))
      (node (ref "U3") (pin "6") (pinfunction "VDD_6") (pintype "passive"))
      (node (ref "U4") (pin "5") (pinfunction "VCC_5") (pintype "passive"))
      (node (ref "U7") (pin "3") (pinfunction "VIN_3") (pintype "passive"))
    )
    (net (code "72") (name "unconnected-(U2-VPP-Pad16)") (class "Default")
      (node (ref "U2") (pin "16") (pinfunction "VPP_16") (pintype "passive+no_connect"))
    )
    (net (code "73") (name "unconnected-(U4-RTS-Pad4)") (class "Default")
      (node (ref "U4") (pin "4") (pinfunction "RTS_4") (pintype "passive+no_connect"))
    )
    (net (code "74") (name "unconnected-(U5-PB5-Pad41)") (class "Default")
      (node (ref "U5") (pin "41") (pinfunction "PB5_41") (pintype "passive+no_connect"))
    )
    (net (code "75") (name "unconnected-(U5-VBAT-Pad1)") (class "Default")
      (node (ref "U5") (pin "1") (pinfunction "VBAT_1") (pintype "passive+no_connect"))
    )
    (net (code "76") (name "unconnected-(U6-CLKOUT-Pad7)") (class "Default")
      (node (ref "U6") (pin "7") (pinfunction "CLKOUT_7") (pintype "passive+no_connect"))
    )
    (net (code "77") (name "unconnected-(U6-INT{slash}-Pad3)") (class "Default")
      (node (ref "U6") (pin "3") (pinfunction "INT/_3") (pintype "passive+no_connect"))
    )
  )
)
